# main.net
KiCad netlist of a schematic drawn in EAGLE
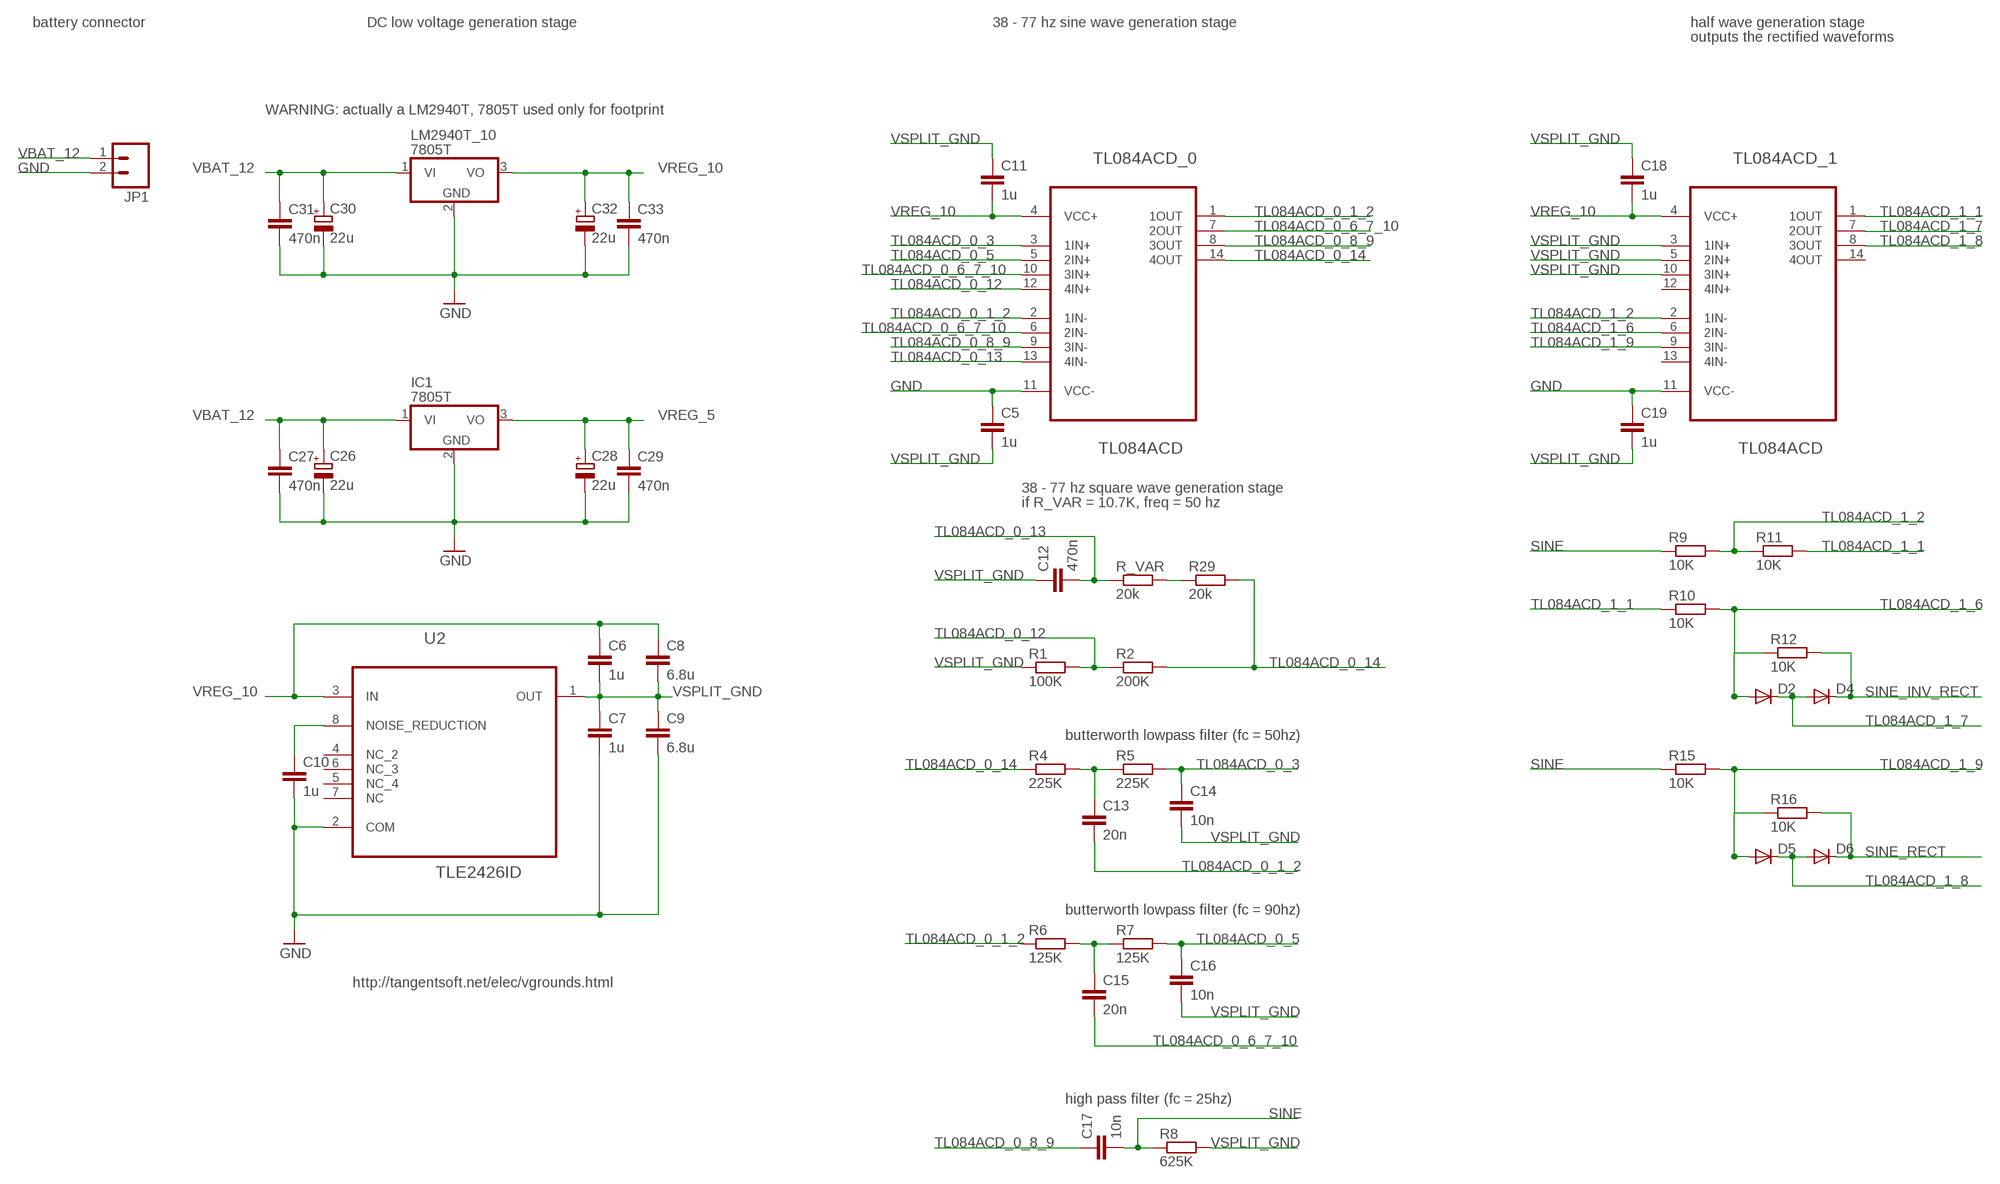
[diagram p0: schematic, sheet 1, part 1 of 2]
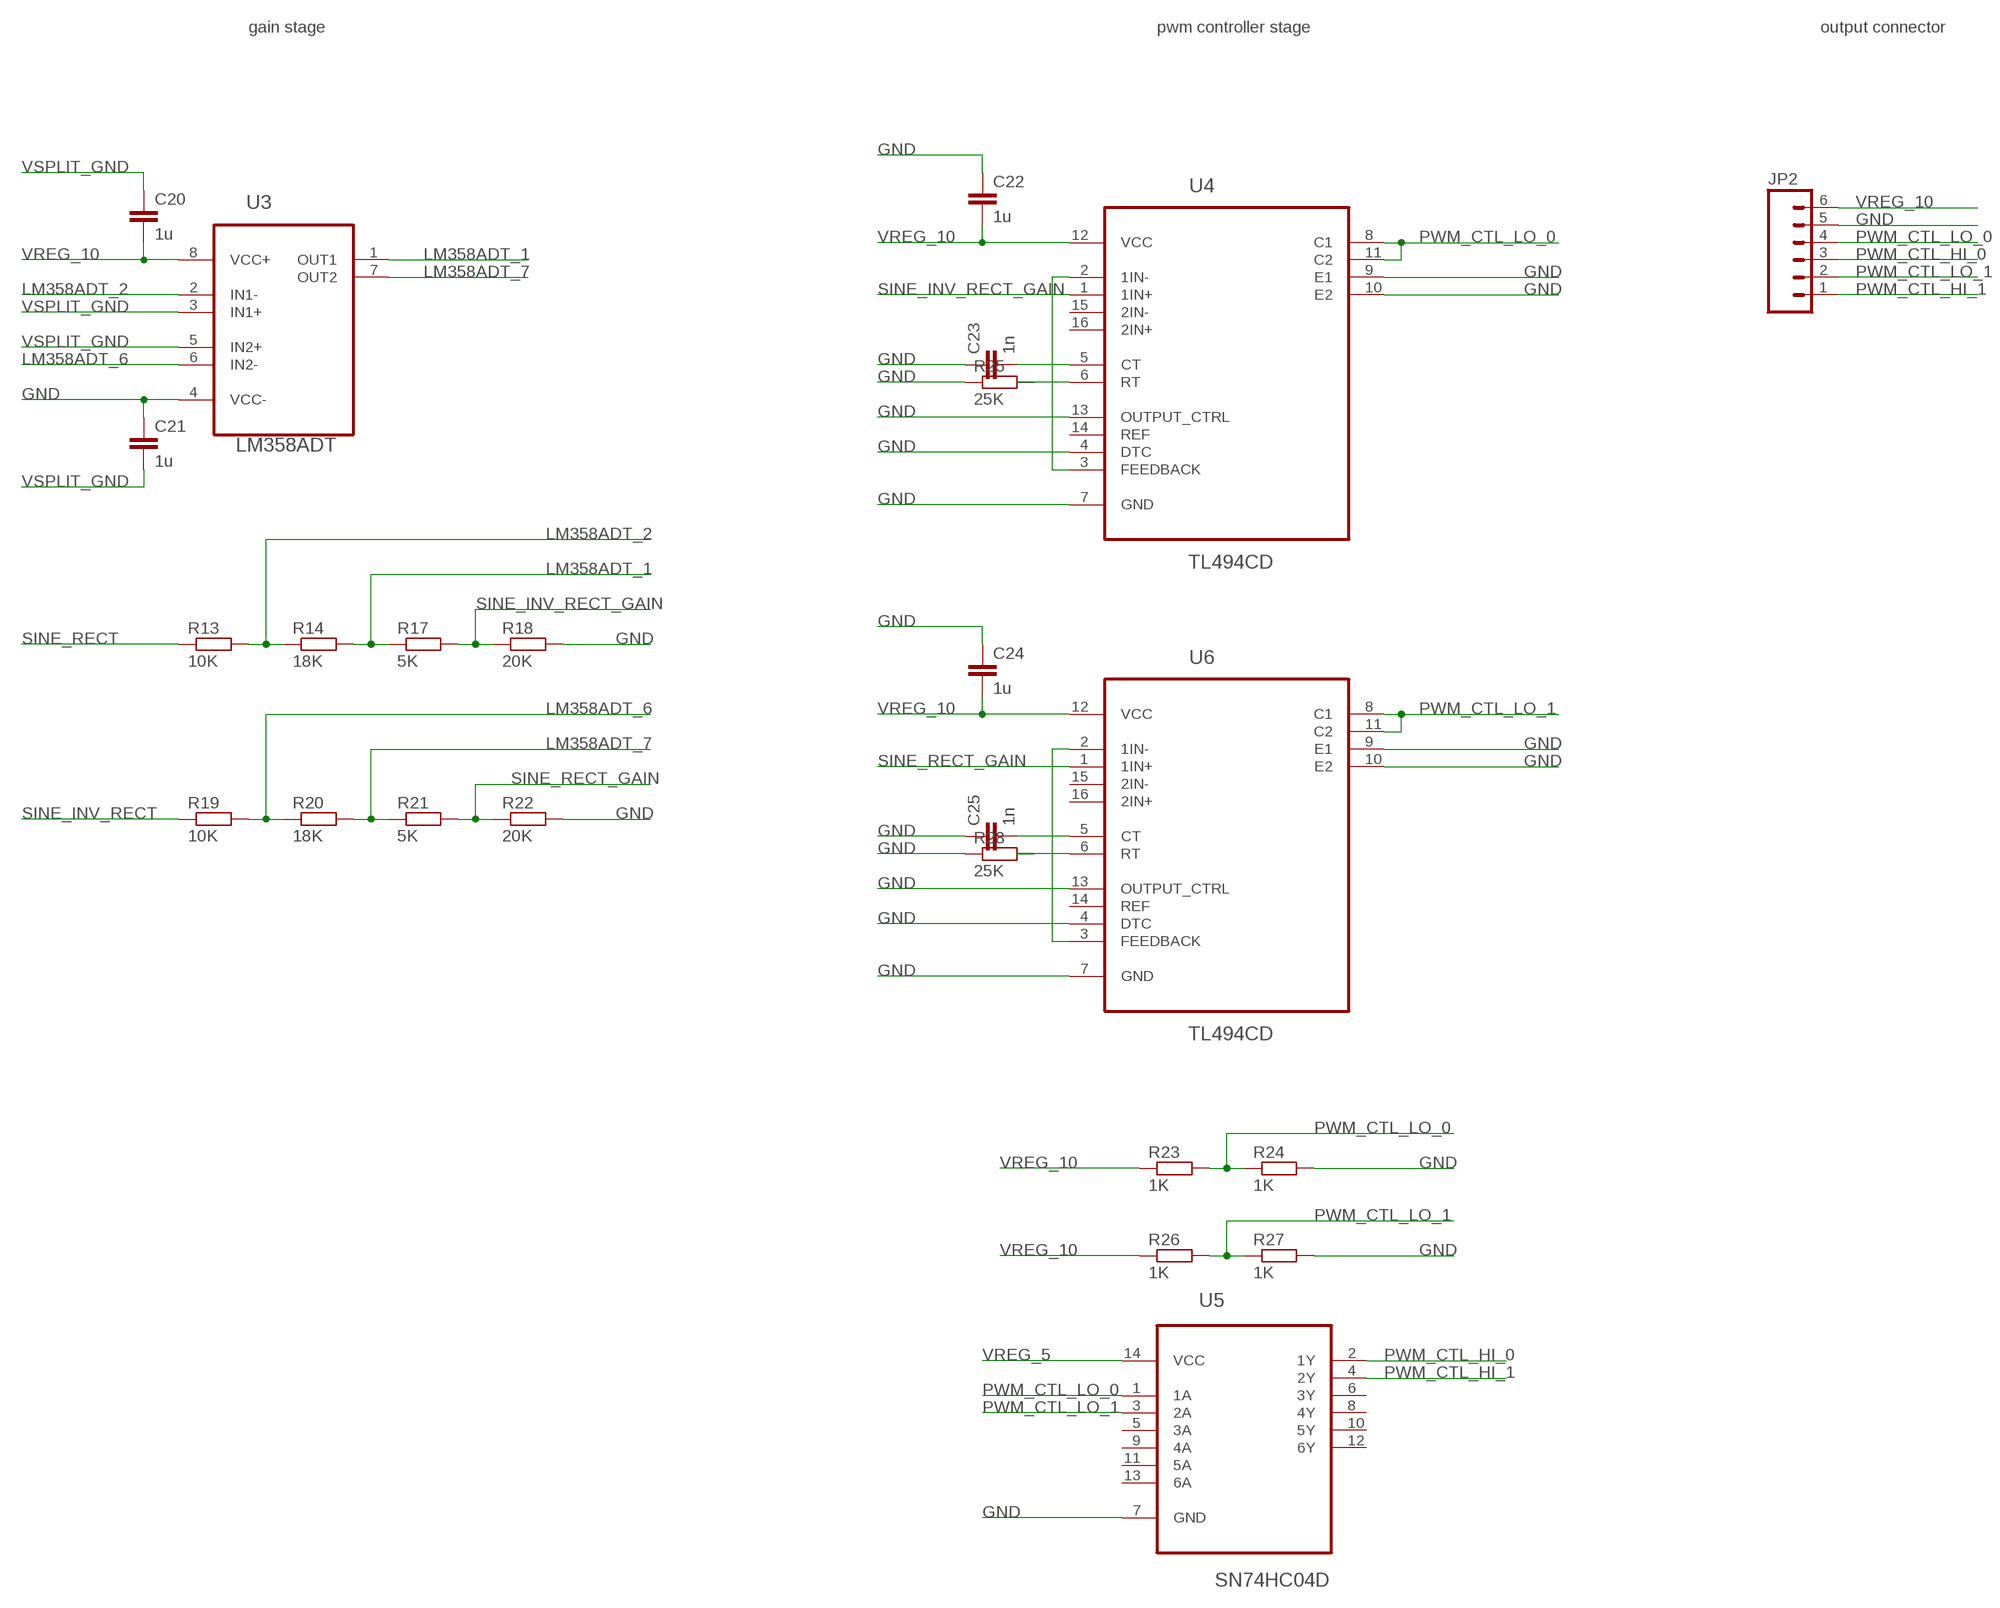
[diagram p1: schematic, sheet 1, part 2 of 2]

(export (version "E")
  (design (tool "Eeschema 10.0.6"))
  (components
    (comp (ref "C5")
      (value "1u")
      (footprint "eagle-import:C1206")
      (libsource (lib "eagle-import") (part "C-EUC1206"))
    )
    (comp (ref "C6")
      (value "1u")
      (footprint "eagle-import:C1206")
      (libsource (lib "eagle-import") (part "C-EUC1206"))
    )
    (comp (ref "C7")
      (value "1u")
      (footprint "eagle-import:C1206")
      (libsource (lib "eagle-import") (part "C-EUC1206"))
    )
    (comp (ref "C8")
      (value "6.8u")
      (footprint "eagle-import:C1206")
      (libsource (lib "eagle-import") (part "C-EUC1206"))
    )
    (comp (ref "C9")
      (value "6.8u")
      (footprint "eagle-import:C1206")
      (libsource (lib "eagle-import") (part "C-EUC1206"))
    )
    (comp (ref "C10")
      (value "1u")
      (footprint "eagle-import:C1206")
      (libsource (lib "eagle-import") (part "C-EUC1206"))
    )
    (comp (ref "C11")
      (value "1u")
      (footprint "eagle-import:C1206")
      (libsource (lib "eagle-import") (part "C-EUC1206"))
    )
    (comp (ref "C12")
      (value "470n")
      (footprint "eagle-import:C1206")
      (libsource (lib "eagle-import") (part "C-EUC1206"))
    )
    (comp (ref "C13")
      (value "20n")
      (footprint "eagle-import:C1206")
      (libsource (lib "eagle-import") (part "C-EUC1206"))
    )
    (comp (ref "C14")
      (value "10n")
      (footprint "eagle-import:C1206")
      (libsource (lib "eagle-import") (part "C-EUC1206"))
    )
    (comp (ref "C15")
      (value "20n")
      (footprint "eagle-import:C1206")
      (libsource (lib "eagle-import") (part "C-EUC1206"))
    )
    (comp (ref "C16")
      (value "10n")
      (footprint "eagle-import:C1206")
      (libsource (lib "eagle-import") (part "C-EUC1206"))
    )
    (comp (ref "C17")
      (value "10n")
      (footprint "eagle-import:C1206")
      (libsource (lib "eagle-import") (part "C-EUC1206"))
    )
    (comp (ref "C18")
      (value "1u")
      (footprint "eagle-import:C1206")
      (libsource (lib "eagle-import") (part "C-EUC1206"))
    )
    (comp (ref "C19")
      (value "1u")
      (footprint "eagle-import:C1206")
      (libsource (lib "eagle-import") (part "C-EUC1206"))
    )
    (comp (ref "C20")
      (value "1u")
      (footprint "eagle-import:C1206")
      (libsource (lib "eagle-import") (part "C-EUC1206"))
    )
    (comp (ref "C21")
      (value "1u")
      (footprint "eagle-import:C1206")
      (libsource (lib "eagle-import") (part "C-EUC1206"))
    )
    (comp (ref "C22")
      (value "1u")
      (footprint "eagle-import:C1206")
      (libsource (lib "eagle-import") (part "C-EUC1206"))
    )
    (comp (ref "C23")
      (value "1n")
      (footprint "eagle-import:C1206")
      (libsource (lib "eagle-import") (part "C-EUC1206"))
    )
    (comp (ref "C24")
      (value "1u")
      (footprint "eagle-import:C1206")
      (libsource (lib "eagle-import") (part "C-EUC1206"))
    )
    (comp (ref "C25")
      (value "1n")
      (footprint "eagle-import:C1206")
      (libsource (lib "eagle-import") (part "C-EUC1206"))
    )
    (comp (ref "C26")
      (value "22u")
      (footprint "eagle-import:085CS_1AR")
      (libsource (lib "eagle-import") (part "CPOL-EU085CS-1AR"))
    )
    (comp (ref "C27")
      (value "470n")
      (footprint "eagle-import:C1206")
      (libsource (lib "eagle-import") (part "C-EUC1206"))
    )
    (comp (ref "C28")
      (value "22u")
      (footprint "eagle-import:085CS_1AR")
      (libsource (lib "eagle-import") (part "CPOL-EU085CS-1AR"))
    )
    (comp (ref "C29")
      (value "470n")
      (footprint "eagle-import:C1206")
      (libsource (lib "eagle-import") (part "C-EUC1206"))
    )
    (comp (ref "C30")
      (value "22u")
      (footprint "eagle-import:085CS_1AR")
      (libsource (lib "eagle-import") (part "CPOL-EU085CS-1AR"))
    )
    (comp (ref "C31")
      (value "470n")
      (footprint "eagle-import:C1206")
      (libsource (lib "eagle-import") (part "C-EUC1206"))
    )
    (comp (ref "C32")
      (value "22u")
      (footprint "eagle-import:085CS_1AR")
      (libsource (lib "eagle-import") (part "CPOL-EU085CS-1AR"))
    )
    (comp (ref "C33")
      (value "470n")
      (footprint "eagle-import:C1206")
      (libsource (lib "eagle-import") (part "C-EUC1206"))
    )
    (comp (ref "D2")
      (value "DIODE-SOD323-W")
      (footprint "eagle-import:SOD323-W")
      (libsource (lib "eagle-import") (part "DIODE-SOD323-W"))
    )
    (comp (ref "D4")
      (value "DIODE-SOD323-W")
      (footprint "eagle-import:SOD323-W")
      (libsource (lib "eagle-import") (part "DIODE-SOD323-W"))
    )
    (comp (ref "D5")
      (value "DIODE-SOD323-W")
      (footprint "eagle-import:SOD323-W")
      (libsource (lib "eagle-import") (part "DIODE-SOD323-W"))
    )
    (comp (ref "D6")
      (value "DIODE-SOD323-W")
      (footprint "eagle-import:SOD323-W")
      (libsource (lib "eagle-import") (part "DIODE-SOD323-W"))
    )
    (comp (ref "IC1")
      (value "7805T")
      (footprint "eagle-import:TO220H")
      (libsource (lib "eagle-import") (part "78T05"))
    )
    (comp (ref "JP1")
      (value "M02LOCK")
      (footprint "eagle-import:1X02_LOCK")
      (libsource (lib "eagle-import") (part "M02LOCK"))
    )
    (comp (ref "JP2")
      (value "M06LOCK")
      (footprint "eagle-import:1X06_LOCK")
      (libsource (lib "eagle-import") (part "M06LOCK"))
    )
    (comp (ref "LM2940T_10")
      (value "7805T")
      (footprint "eagle-import:TO220H")
      (libsource (lib "eagle-import") (part "78T05"))
    )
    (comp (ref "R1")
      (value "100K")
      (footprint "eagle-import:M1206")
      (libsource (lib "eagle-import") (part "R-EU_M1206"))
    )
    (comp (ref "R2")
      (value "200K")
      (footprint "eagle-import:M1206")
      (libsource (lib "eagle-import") (part "R-EU_M1206"))
    )
    (comp (ref "R4")
      (value "225K")
      (footprint "eagle-import:M1206")
      (libsource (lib "eagle-import") (part "R-EU_M1206"))
    )
    (comp (ref "R5")
      (value "225K")
      (footprint "eagle-import:M1206")
      (libsource (lib "eagle-import") (part "R-EU_M1206"))
    )
    (comp (ref "R6")
      (value "125K")
      (footprint "eagle-import:M1206")
      (libsource (lib "eagle-import") (part "R-EU_M1206"))
    )
    (comp (ref "R7")
      (value "125K")
      (footprint "eagle-import:M1206")
      (libsource (lib "eagle-import") (part "R-EU_M1206"))
    )
    (comp (ref "R8")
      (value "625K")
      (footprint "eagle-import:M1206")
      (libsource (lib "eagle-import") (part "R-EU_M1206"))
    )
    (comp (ref "R9")
      (value "10K")
      (footprint "eagle-import:M1206")
      (libsource (lib "eagle-import") (part "R-EU_M1206"))
    )
    (comp (ref "R10")
      (value "10K")
      (footprint "eagle-import:M1206")
      (libsource (lib "eagle-import") (part "R-EU_M1206"))
    )
    (comp (ref "R11")
      (value "10K")
      (footprint "eagle-import:M1206")
      (libsource (lib "eagle-import") (part "R-EU_M1206"))
    )
    (comp (ref "R12")
      (value "10K")
      (footprint "eagle-import:M1206")
      (libsource (lib "eagle-import") (part "R-EU_M1206"))
    )
    (comp (ref "R13")
      (value "10K")
      (footprint "eagle-import:M1206")
      (libsource (lib "eagle-import") (part "R-EU_M1206"))
    )
    (comp (ref "R14")
      (value "18K")
      (footprint "eagle-import:M1206")
      (libsource (lib "eagle-import") (part "R-EU_M1206"))
    )
    (comp (ref "R15")
      (value "10K")
      (footprint "eagle-import:M1206")
      (libsource (lib "eagle-import") (part "R-EU_M1206"))
    )
    (comp (ref "R16")
      (value "10K")
      (footprint "eagle-import:M1206")
      (libsource (lib "eagle-import") (part "R-EU_M1206"))
    )
    (comp (ref "R17")
      (value "5K")
      (footprint "eagle-import:M1206")
      (libsource (lib "eagle-import") (part "R-EU_M1206"))
    )
    (comp (ref "R18")
      (value "20K")
      (footprint "eagle-import:M1206")
      (libsource (lib "eagle-import") (part "R-EU_M1206"))
    )
    (comp (ref "R19")
      (value "10K")
      (footprint "eagle-import:M1206")
      (libsource (lib "eagle-import") (part "R-EU_M1206"))
    )
    (comp (ref "R20")
      (value "18K")
      (footprint "eagle-import:M1206")
      (libsource (lib "eagle-import") (part "R-EU_M1206"))
    )
    (comp (ref "R21")
      (value "5K")
      (footprint "eagle-import:M1206")
      (libsource (lib "eagle-import") (part "R-EU_M1206"))
    )
    (comp (ref "R22")
      (value "20K")
      (footprint "eagle-import:M1206")
      (libsource (lib "eagle-import") (part "R-EU_M1206"))
    )
    (comp (ref "R23")
      (value "1K")
      (footprint "eagle-import:M1206")
      (libsource (lib "eagle-import") (part "R-EU_M1206"))
    )
    (comp (ref "R24")
      (value "1K")
      (footprint "eagle-import:M1206")
      (libsource (lib "eagle-import") (part "R-EU_M1206"))
    )
    (comp (ref "R25")
      (value "25K")
      (footprint "eagle-import:M1206")
      (libsource (lib "eagle-import") (part "R-EU_M1206"))
    )
    (comp (ref "R26")
      (value "1K")
      (footprint "eagle-import:M1206")
      (libsource (lib "eagle-import") (part "R-EU_M1206"))
    )
    (comp (ref "R27")
      (value "1K")
      (footprint "eagle-import:M1206")
      (libsource (lib "eagle-import") (part "R-EU_M1206"))
    )
    (comp (ref "R28")
      (value "25K")
      (footprint "eagle-import:M1206")
      (libsource (lib "eagle-import") (part "R-EU_M1206"))
    )
    (comp (ref "R29")
      (value "20k")
      (footprint "eagle-import:M1206")
      (libsource (lib "eagle-import") (part "R-EU_M1206"))
    )
    (comp (ref "R_VAR")
      (value "20k")
      (footprint "eagle-import:M1206")
      (libsource (lib "eagle-import") (part "R-EU_M1206"))
    )
    (comp (ref "TL084ACD_0")
      (value "TL084ACD")
      (footprint "eagle-import:SOIC127P600X175-14N")
      (libsource (lib "eagle-import") (part "TL084ACD"))
    )
    (comp (ref "TL084ACD_1")
      (value "TL084ACD")
      (footprint "eagle-import:SOIC127P600X175-14N")
      (libsource (lib "eagle-import") (part "TL084ACD"))
    )
    (comp (ref "U2")
      (value "TLE2426ID")
      (footprint "eagle-import:SOIC127P600X175-8N")
      (libsource (lib "eagle-import") (part "TLE2426ID"))
    )
    (comp (ref "U3")
      (value "LM358ADT")
      (footprint "eagle-import:SOIC127P600X175-8N")
      (libsource (lib "eagle-import") (part "LM358ADT"))
    )
    (comp (ref "U4")
      (value "TL494CD")
      (footprint "eagle-import:SOIC127P600X175-16N")
      (libsource (lib "eagle-import") (part "TL494CD"))
    )
    (comp (ref "U5")
      (value "SN74HC04D")
      (footprint "eagle-import:SOIC127P600X175-14N")
      (libsource (lib "eagle-import") (part "SN74HC04D"))
    )
    (comp (ref "U6")
      (value "TL494CD")
      (footprint "eagle-import:SOIC127P600X175-16N")
      (libsource (lib "eagle-import") (part "TL494CD"))
    )
  )
  (nets
    (net (code "1") (name "/LM358ADT_1") (class "Default")
      (node (ref "R14") (pin "2") (pinfunction "2_2") (pintype "passive"))
      (node (ref "R17") (pin "1") (pinfunction "1_1") (pintype "passive"))
      (node (ref "U3") (pin "1") (pinfunction "OUT1_1") (pintype "output"))
    )
    (net (code "2") (name "/LM358ADT_2") (class "Default")
      (node (ref "R13") (pin "2") (pinfunction "2_2") (pintype "passive"))
      (node (ref "R14") (pin "1") (pinfunction "1_1") (pintype "passive"))
      (node (ref "U3") (pin "2") (pinfunction "IN1-_2") (pintype "input"))
    )
    (net (code "3") (name "/LM358ADT_6") (class "Default")
      (node (ref "R19") (pin "2") (pinfunction "2_2") (pintype "passive"))
      (node (ref "R20") (pin "1") (pinfunction "1_1") (pintype "passive"))
      (node (ref "U3") (pin "6") (pinfunction "IN2-_6") (pintype "input"))
    )
    (net (code "4") (name "/LM358ADT_7") (class "Default")
      (node (ref "R20") (pin "2") (pinfunction "2_2") (pintype "passive"))
      (node (ref "R21") (pin "1") (pinfunction "1_1") (pintype "passive"))
      (node (ref "U3") (pin "7") (pinfunction "OUT2_7") (pintype "output"))
    )
    (net (code "5") (name "/PWM_CTL_HI_0") (class "Default")
      (node (ref "JP2") (pin "3") (pinfunction "3_3") (pintype "passive"))
      (node (ref "U5") (pin "2") (pinfunction "1Y_2") (pintype "output"))
    )
    (net (code "6") (name "/PWM_CTL_HI_1") (class "Default")
      (node (ref "JP2") (pin "1") (pinfunction "1_1") (pintype "passive"))
      (node (ref "U5") (pin "4") (pinfunction "2Y_4") (pintype "output"))
    )
    (net (code "7") (name "/PWM_CTL_LO_0") (class "Default")
      (node (ref "JP2") (pin "4") (pinfunction "4_4") (pintype "passive"))
      (node (ref "R23") (pin "2") (pinfunction "2_2") (pintype "passive"))
      (node (ref "R24") (pin "1") (pinfunction "1_1") (pintype "passive"))
      (node (ref "U4") (pin "11") (pinfunction "C2_11") (pintype "output"))
      (node (ref "U4") (pin "8") (pinfunction "C1_8") (pintype "output"))
      (node (ref "U5") (pin "1") (pinfunction "1A_1") (pintype "input"))
    )
    (net (code "8") (name "/PWM_CTL_LO_1") (class "Default")
      (node (ref "JP2") (pin "2") (pinfunction "2_2") (pintype "passive"))
      (node (ref "R26") (pin "2") (pinfunction "2_2") (pintype "passive"))
      (node (ref "R27") (pin "1") (pinfunction "1_1") (pintype "passive"))
      (node (ref "U5") (pin "3") (pinfunction "2A_3") (pintype "input"))
      (node (ref "U6") (pin "11") (pinfunction "C2_11") (pintype "output"))
      (node (ref "U6") (pin "8") (pinfunction "C1_8") (pintype "output"))
    )
    (net (code "9") (name "/SINE") (class "Default")
      (node (ref "C17") (pin "2") (pinfunction "2_2") (pintype "passive"))
      (node (ref "R15") (pin "1") (pinfunction "1_1") (pintype "passive"))
      (node (ref "R8") (pin "1") (pinfunction "1_1") (pintype "passive"))
      (node (ref "R9") (pin "1") (pinfunction "1_1") (pintype "passive"))
    )
    (net (code "10") (name "/SINE_INV_RECT") (class "Default")
      (node (ref "D4") (pin "C") (pinfunction "C_C") (pintype "passive"))
      (node (ref "R12") (pin "2") (pinfunction "2_2") (pintype "passive"))
      (node (ref "R19") (pin "1") (pinfunction "1_1") (pintype "passive"))
    )
    (net (code "11") (name "/SINE_INV_RECT_GAIN") (class "Default")
      (node (ref "R17") (pin "2") (pinfunction "2_2") (pintype "passive"))
      (node (ref "R18") (pin "1") (pinfunction "1_1") (pintype "passive"))
      (node (ref "U4") (pin "1") (pinfunction "1IN+_1") (pintype "input"))
    )
    (net (code "12") (name "/SINE_RECT") (class "Default")
      (node (ref "D6") (pin "C") (pinfunction "C_C") (pintype "passive"))
      (node (ref "R13") (pin "1") (pinfunction "1_1") (pintype "passive"))
      (node (ref "R16") (pin "2") (pinfunction "2_2") (pintype "passive"))
    )
    (net (code "13") (name "/SINE_RECT_GAIN") (class "Default")
      (node (ref "R21") (pin "2") (pinfunction "2_2") (pintype "passive"))
      (node (ref "R22") (pin "1") (pinfunction "1_1") (pintype "passive"))
      (node (ref "U6") (pin "1") (pinfunction "1IN+_1") (pintype "input"))
    )
    (net (code "14") (name "/TL084ACD_0_1_2") (class "Default")
      (node (ref "C13") (pin "2") (pinfunction "2_2") (pintype "passive"))
      (node (ref "R6") (pin "1") (pinfunction "1_1") (pintype "passive"))
      (node (ref "TL084ACD_0") (pin "1") (pinfunction "1OUT_1") (pintype "output"))
      (node (ref "TL084ACD_0") (pin "2") (pinfunction "1IN-_2") (pintype "input"))
    )
    (net (code "15") (name "/TL084ACD_0_3") (class "Default")
      (node (ref "C14") (pin "1") (pinfunction "1_1") (pintype "passive"))
      (node (ref "R5") (pin "2") (pinfunction "2_2") (pintype "passive"))
      (node (ref "TL084ACD_0") (pin "3") (pinfunction "1IN+_3") (pintype "input"))
    )
    (net (code "16") (name "/TL084ACD_0_5") (class "Default")
      (node (ref "C16") (pin "1") (pinfunction "1_1") (pintype "passive"))
      (node (ref "R7") (pin "2") (pinfunction "2_2") (pintype "passive"))
      (node (ref "TL084ACD_0") (pin "5") (pinfunction "2IN+_5") (pintype "input"))
    )
    (net (code "17") (name "/TL084ACD_0_6_7_10") (class "Default")
      (node (ref "C15") (pin "2") (pinfunction "2_2") (pintype "passive"))
      (node (ref "TL084ACD_0") (pin "10") (pinfunction "3IN+_10") (pintype "input"))
      (node (ref "TL084ACD_0") (pin "6") (pinfunction "2IN-_6") (pintype "input"))
      (node (ref "TL084ACD_0") (pin "7") (pinfunction "2OUT_7") (pintype "output"))
    )
    (net (code "18") (name "/TL084ACD_0_8_9") (class "Default")
      (node (ref "C17") (pin "1") (pinfunction "1_1") (pintype "passive"))
      (node (ref "TL084ACD_0") (pin "8") (pinfunction "3OUT_8") (pintype "output"))
      (node (ref "TL084ACD_0") (pin "9") (pinfunction "3IN-_9") (pintype "input"))
    )
    (net (code "19") (name "/TL084ACD_0_12") (class "Default")
      (node (ref "R1") (pin "2") (pinfunction "2_2") (pintype "passive"))
      (node (ref "R2") (pin "1") (pinfunction "1_1") (pintype "passive"))
      (node (ref "TL084ACD_0") (pin "12") (pinfunction "4IN+_12") (pintype "input"))
    )
    (net (code "20") (name "/TL084ACD_0_13") (class "Default")
      (node (ref "C12") (pin "2") (pinfunction "2_2") (pintype "passive"))
      (node (ref "R_VAR") (pin "1") (pinfunction "1_1") (pintype "passive"))
      (node (ref "TL084ACD_0") (pin "13") (pinfunction "4IN-_13") (pintype "input"))
    )
    (net (code "21") (name "/TL084ACD_0_14") (class "Default")
      (node (ref "R2") (pin "2") (pinfunction "2_2") (pintype "passive"))
      (node (ref "R29") (pin "2") (pinfunction "2_2") (pintype "passive"))
      (node (ref "R4") (pin "1") (pinfunction "1_1") (pintype "passive"))
      (node (ref "TL084ACD_0") (pin "14") (pinfunction "4OUT_14") (pintype "output"))
    )
    (net (code "22") (name "/TL084ACD_1_1") (class "Default")
      (node (ref "R10") (pin "1") (pinfunction "1_1") (pintype "passive"))
      (node (ref "R11") (pin "2") (pinfunction "2_2") (pintype "passive"))
      (node (ref "TL084ACD_1") (pin "1") (pinfunction "1OUT_1") (pintype "output"))
    )
    (net (code "23") (name "/TL084ACD_1_2") (class "Default")
      (node (ref "R11") (pin "1") (pinfunction "1_1") (pintype "passive"))
      (node (ref "R9") (pin "2") (pinfunction "2_2") (pintype "passive"))
      (node (ref "TL084ACD_1") (pin "2") (pinfunction "1IN-_2") (pintype "input"))
    )
    (net (code "24") (name "/TL084ACD_1_6") (class "Default")
      (node (ref "D2") (pin "A") (pinfunction "A_A") (pintype "passive"))
      (node (ref "R10") (pin "2") (pinfunction "2_2") (pintype "passive"))
      (node (ref "R12") (pin "1") (pinfunction "1_1") (pintype "passive"))
      (node (ref "TL084ACD_1") (pin "6") (pinfunction "2IN-_6") (pintype "input"))
    )
    (net (code "25") (name "/TL084ACD_1_7") (class "Default")
      (node (ref "D2") (pin "C") (pinfunction "C_C") (pintype "passive"))
      (node (ref "D4") (pin "A") (pinfunction "A_A") (pintype "passive"))
      (node (ref "TL084ACD_1") (pin "7") (pinfunction "2OUT_7") (pintype "output"))
    )
    (net (code "26") (name "/TL084ACD_1_8") (class "Default")
      (node (ref "D5") (pin "C") (pinfunction "C_C") (pintype "passive"))
      (node (ref "D6") (pin "A") (pinfunction "A_A") (pintype "passive"))
      (node (ref "TL084ACD_1") (pin "8") (pinfunction "3OUT_8") (pintype "output"))
    )
    (net (code "27") (name "/TL084ACD_1_9") (class "Default")
      (node (ref "D5") (pin "A") (pinfunction "A_A") (pintype "passive"))
      (node (ref "R15") (pin "2") (pinfunction "2_2") (pintype "passive"))
      (node (ref "R16") (pin "1") (pinfunction "1_1") (pintype "passive"))
      (node (ref "TL084ACD_1") (pin "9") (pinfunction "3IN-_9") (pintype "input"))
    )
    (net (code "28") (name "/VBAT_12") (class "Default")
      (node (ref "C26") (pin "+") (pinfunction "+_+") (pintype "passive"))
      (node (ref "C27") (pin "1") (pinfunction "1_1") (pintype "passive"))
      (node (ref "C30") (pin "+") (pinfunction "+_+") (pintype "passive"))
      (node (ref "C31") (pin "1") (pinfunction "1_1") (pintype "passive"))
      (node (ref "IC1") (pin "1") (pinfunction "VI_1") (pintype "input"))
      (node (ref "JP1") (pin "1") (pinfunction "1_1") (pintype "passive"))
      (node (ref "LM2940T_10") (pin "1") (pinfunction "VI_1") (pintype "input"))
    )
    (net (code "29") (name "/VREG_5") (class "Default")
      (node (ref "C28") (pin "+") (pinfunction "+_+") (pintype "passive"))
      (node (ref "C29") (pin "1") (pinfunction "1_1") (pintype "passive"))
      (node (ref "IC1") (pin "3") (pinfunction "VO_3") (pintype "passive"))
      (node (ref "U5") (pin "14") (pinfunction "VCC_14") (pintype "power_in"))
    )
    (net (code "30") (name "/VREG_10") (class "Default")
      (node (ref "C11") (pin "2") (pinfunction "2_2") (pintype "passive"))
      (node (ref "C18") (pin "2") (pinfunction "2_2") (pintype "passive"))
      (node (ref "C20") (pin "2") (pinfunction "2_2") (pintype "passive"))
      (node (ref "C22") (pin "2") (pinfunction "2_2") (pintype "passive"))
      (node (ref "C24") (pin "2") (pinfunction "2_2") (pintype "passive"))
      (node (ref "C32") (pin "+") (pinfunction "+_+") (pintype "passive"))
      (node (ref "C33") (pin "1") (pinfunction "1_1") (pintype "passive"))
      (node (ref "C6") (pin "1") (pinfunction "1_1") (pintype "passive"))
      (node (ref "C8") (pin "1") (pinfunction "1_1") (pintype "passive"))
      (node (ref "JP2") (pin "6") (pinfunction "6_6") (pintype "passive"))
      (node (ref "LM2940T_10") (pin "3") (pinfunction "VO_3") (pintype "passive"))
      (node (ref "R23") (pin "1") (pinfunction "1_1") (pintype "passive"))
      (node (ref "R26") (pin "1") (pinfunction "1_1") (pintype "passive"))
      (node (ref "TL084ACD_0") (pin "4") (pinfunction "VCC+_4") (pintype "power_in"))
      (node (ref "TL084ACD_1") (pin "4") (pinfunction "VCC+_4") (pintype "power_in"))
      (node (ref "U2") (pin "3") (pinfunction "IN_3") (pintype "input"))
      (node (ref "U3") (pin "8") (pinfunction "VCC+_8") (pintype "power_in"))
      (node (ref "U4") (pin "12") (pinfunction "VCC_12") (pintype "power_in"))
      (node (ref "U6") (pin "12") (pinfunction "VCC_12") (pintype "power_in"))
    )
    (net (code "31") (name "/VSPLIT_GND") (class "Default")
      (node (ref "C11") (pin "1") (pinfunction "1_1") (pintype "passive"))
      (node (ref "C12") (pin "1") (pinfunction "1_1") (pintype "passive"))
      (node (ref "C14") (pin "2") (pinfunction "2_2") (pintype "passive"))
      (node (ref "C16") (pin "2") (pinfunction "2_2") (pintype "passive"))
      (node (ref "C18") (pin "1") (pinfunction "1_1") (pintype "passive"))
      (node (ref "C19") (pin "2") (pinfunction "2_2") (pintype "passive"))
      (node (ref "C20") (pin "1") (pinfunction "1_1") (pintype "passive"))
      (node (ref "C21") (pin "2") (pinfunction "2_2") (pintype "passive"))
      (node (ref "C5") (pin "2") (pinfunction "2_2") (pintype "passive"))
      (node (ref "C6") (pin "2") (pinfunction "2_2") (pintype "passive"))
      (node (ref "C7") (pin "1") (pinfunction "1_1") (pintype "passive"))
      (node (ref "C8") (pin "2") (pinfunction "2_2") (pintype "passive"))
      (node (ref "C9") (pin "1") (pinfunction "1_1") (pintype "passive"))
      (node (ref "R1") (pin "1") (pinfunction "1_1") (pintype "passive"))
      (node (ref "R8") (pin "2") (pinfunction "2_2") (pintype "passive"))
      (node (ref "TL084ACD_1") (pin "10") (pinfunction "3IN+_10") (pintype "input"))
      (node (ref "TL084ACD_1") (pin "3") (pinfunction "1IN+_3") (pintype "input"))
      (node (ref "TL084ACD_1") (pin "5") (pinfunction "2IN+_5") (pintype "input"))
      (node (ref "U2") (pin "1") (pinfunction "OUT_1") (pintype "output"))
      (node (ref "U3") (pin "3") (pinfunction "IN1+_3") (pintype "input"))
      (node (ref "U3") (pin "5") (pinfunction "IN2+_5") (pintype "input"))
    )
    (net (code "32") (name "GND") (class "Default")
      (node (ref "C10") (pin "2") (pinfunction "2_2") (pintype "passive"))
      (node (ref "C19") (pin "1") (pinfunction "1_1") (pintype "passive"))
      (node (ref "C21") (pin "1") (pinfunction "1_1") (pintype "passive"))
      (node (ref "C22") (pin "1") (pinfunction "1_1") (pintype "passive"))
      (node (ref "C23") (pin "1") (pinfunction "1_1") (pintype "passive"))
      (node (ref "C24") (pin "1") (pinfunction "1_1") (pintype "passive"))
      (node (ref "C25") (pin "1") (pinfunction "1_1") (pintype "passive"))
      (node (ref "C26") (pin "-") (pinfunction "-_-") (pintype "passive"))
      (node (ref "C27") (pin "2") (pinfunction "2_2") (pintype "passive"))
      (node (ref "C28") (pin "-") (pinfunction "-_-") (pintype "passive"))
      (node (ref "C29") (pin "2") (pinfunction "2_2") (pintype "passive"))
      (node (ref "C30") (pin "-") (pinfunction "-_-") (pintype "passive"))
      (node (ref "C31") (pin "2") (pinfunction "2_2") (pintype "passive"))
      (node (ref "C32") (pin "-") (pinfunction "-_-") (pintype "passive"))
      (node (ref "C33") (pin "2") (pinfunction "2_2") (pintype "passive"))
      (node (ref "C5") (pin "1") (pinfunction "1_1") (pintype "passive"))
      (node (ref "C7") (pin "2") (pinfunction "2_2") (pintype "passive"))
      (node (ref "C9") (pin "2") (pinfunction "2_2") (pintype "passive"))
      (node (ref "IC1") (pin "2") (pinfunction "GND_2") (pintype "passive"))
      (node (ref "JP1") (pin "2") (pinfunction "2_2") (pintype "passive"))
      (node (ref "JP2") (pin "5") (pinfunction "5_5") (pintype "passive"))
      (node (ref "LM2940T_10") (pin "2") (pinfunction "GND_2") (pintype "passive"))
      (node (ref "R18") (pin "2") (pinfunction "2_2") (pintype "passive"))
      (node (ref "R22") (pin "2") (pinfunction "2_2") (pintype "passive"))
      (node (ref "R24") (pin "2") (pinfunction "2_2") (pintype "passive"))
      (node (ref "R25") (pin "1") (pinfunction "1_1") (pintype "passive"))
      (node (ref "R27") (pin "2") (pinfunction "2_2") (pintype "passive"))
      (node (ref "R28") (pin "1") (pinfunction "1_1") (pintype "passive"))
      (node (ref "TL084ACD_0") (pin "11") (pinfunction "VCC-_11") (pintype "power_in"))
      (node (ref "TL084ACD_1") (pin "11") (pinfunction "VCC-_11") (pintype "power_in"))
      (node (ref "U2") (pin "2") (pinfunction "COM_2") (pintype "passive"))
      (node (ref "U3") (pin "4") (pinfunction "VCC-_4") (pintype "power_in"))
      (node (ref "U4") (pin "10") (pinfunction "E2_10") (pintype "output"))
      (node (ref "U4") (pin "13") (pinfunction "OUTPUT_CTRL_13") (pintype "passive"))
      (node (ref "U4") (pin "4") (pinfunction "DTC_4") (pintype "input"))
      (node (ref "U4") (pin "7") (pinfunction "GND_7") (pintype "passive"))
      (node (ref "U4") (pin "9") (pinfunction "E1_9") (pintype "output"))
      (node (ref "U5") (pin "7") (pinfunction "GND_7") (pintype "passive"))
      (node (ref "U6") (pin "10") (pinfunction "E2_10") (pintype "output"))
      (node (ref "U6") (pin "13") (pinfunction "OUTPUT_CTRL_13") (pintype "passive"))
      (node (ref "U6") (pin "4") (pinfunction "DTC_4") (pintype "input"))
      (node (ref "U6") (pin "7") (pinfunction "GND_7") (pintype "passive"))
      (node (ref "U6") (pin "9") (pinfunction "E1_9") (pintype "output"))
    )
    (net (code "33") (name "Net-(C13-Pad1)") (class "Default")
      (node (ref "C13") (pin "1") (pinfunction "1_1") (pintype "passive"))
      (node (ref "R4") (pin "2") (pinfunction "2_2") (pintype "passive"))
      (node (ref "R5") (pin "1") (pinfunction "1_1") (pintype "passive"))
    )
    (net (code "34") (name "Net-(C15-Pad1)") (class "Default")
      (node (ref "C15") (pin "1") (pinfunction "1_1") (pintype "passive"))
      (node (ref "R6") (pin "2") (pinfunction "2_2") (pintype "passive"))
      (node (ref "R7") (pin "1") (pinfunction "1_1") (pintype "passive"))
    )
    (net (code "35") (name "Net-(R29-Pad1)") (class "Default")
      (node (ref "R29") (pin "1") (pinfunction "1_1") (pintype "passive"))
      (node (ref "R_VAR") (pin "2") (pinfunction "2_2") (pintype "passive"))
    )
    (net (code "36") (name "Net-(U2-NOISE_REDUCTION)") (class "Default")
      (node (ref "C10") (pin "1") (pinfunction "1_1") (pintype "passive"))
      (node (ref "U2") (pin "8") (pinfunction "NOISE_REDUCTION_8") (pintype "passive"))
    )
    (net (code "37") (name "Net-(U4-1IN-)") (class "Default")
      (node (ref "U4") (pin "2") (pinfunction "1IN-_2") (pintype "input"))
      (node (ref "U4") (pin "3") (pinfunction "FEEDBACK_3") (pintype "input"))
    )
    (net (code "38") (name "Net-(U4-CT)") (class "Default")
      (node (ref "C23") (pin "2") (pinfunction "2_2") (pintype "passive"))
      (node (ref "U4") (pin "5") (pinfunction "CT_5") (pintype "input"))
    )
    (net (code "39") (name "Net-(U4-RT)") (class "Default")
      (node (ref "R25") (pin "2") (pinfunction "2_2") (pintype "passive"))
      (node (ref "U4") (pin "6") (pinfunction "RT_6") (pintype "input"))
    )
    (net (code "40") (name "Net-(U6-1IN-)") (class "Default")
      (node (ref "U6") (pin "2") (pinfunction "1IN-_2") (pintype "input"))
      (node (ref "U6") (pin "3") (pinfunction "FEEDBACK_3") (pintype "input"))
    )
    (net (code "41") (name "Net-(U6-CT)") (class "Default")
      (node (ref "C25") (pin "2") (pinfunction "2_2") (pintype "passive"))
      (node (ref "U6") (pin "5") (pinfunction "CT_5") (pintype "input"))
    )
    (net (code "42") (name "Net-(U6-RT)") (class "Default")
      (node (ref "R28") (pin "2") (pinfunction "2_2") (pintype "passive"))
      (node (ref "U6") (pin "6") (pinfunction "RT_6") (pintype "input"))
    )
    (net (code "43") (name "unconnected-(TL084ACD_1-4IN+-Pad12)") (class "Default")
      (node (ref "TL084ACD_1") (pin "12") (pinfunction "4IN+_12") (pintype "input"))
    )
    (net (code "44") (name "unconnected-(TL084ACD_1-4IN--Pad13)") (class "Default")
      (node (ref "TL084ACD_1") (pin "13") (pinfunction "4IN-_13") (pintype "input"))
    )
    (net (code "45") (name "unconnected-(TL084ACD_1-4OUT-Pad14)") (class "Default")
      (node (ref "TL084ACD_1") (pin "14") (pinfunction "4OUT_14") (pintype "output"))
    )
    (net (code "46") (name "unconnected-(U2-NC-Pad7)") (class "Default")
      (node (ref "U2") (pin "7") (pinfunction "NC_7") (pintype "no_connect"))
    )
    (net (code "47") (name "unconnected-(U2-NC_2-Pad4)") (class "Default")
      (node (ref "U2") (pin "4") (pinfunction "NC_2_4") (pintype "no_connect"))
    )
    (net (code "48") (name "unconnected-(U2-NC_3-Pad6)") (class "Default")
      (node (ref "U2") (pin "6") (pinfunction "NC_3_6") (pintype "no_connect"))
    )
    (net (code "49") (name "unconnected-(U2-NC_4-Pad5)") (class "Default")
      (node (ref "U2") (pin "5") (pinfunction "NC_4_5") (pintype "no_connect"))
    )
    (net (code "50") (name "unconnected-(U4-2IN+-Pad16)") (class "Default")
      (node (ref "U4") (pin "16") (pinfunction "2IN+_16") (pintype "input"))
    )
    (net (code "51") (name "unconnected-(U4-2IN--Pad15)") (class "Default")
      (node (ref "U4") (pin "15") (pinfunction "2IN-_15") (pintype "input"))
    )
    (net (code "52") (name "unconnected-(U4-REF-Pad14)") (class "Default")
      (node (ref "U4") (pin "14") (pinfunction "REF_14") (pintype "input"))
    )
    (net (code "53") (name "unconnected-(U5-3A-Pad5)") (class "Default")
      (node (ref "U5") (pin "5") (pinfunction "3A_5") (pintype "input"))
    )
    (net (code "54") (name "unconnected-(U5-3Y-Pad6)") (class "Default")
      (node (ref "U5") (pin "6") (pinfunction "3Y_6") (pintype "output"))
    )
    (net (code "55") (name "unconnected-(U5-4A-Pad9)") (class "Default")
      (node (ref "U5") (pin "9") (pinfunction "4A_9") (pintype "input"))
    )
    (net (code "56") (name "unconnected-(U5-4Y-Pad8)") (class "Default")
      (node (ref "U5") (pin "8") (pinfunction "4Y_8") (pintype "output"))
    )
    (net (code "57") (name "unconnected-(U5-5A-Pad11)") (class "Default")
      (node (ref "U5") (pin "11") (pinfunction "5A_11") (pintype "input"))
    )
    (net (code "58") (name "unconnected-(U5-5Y-Pad10)") (class "Default")
      (node (ref "U5") (pin "10") (pinfunction "5Y_10") (pintype "output"))
    )
    (net (code "59") (name "unconnected-(U5-6A-Pad13)") (class "Default")
      (node (ref "U5") (pin "13") (pinfunction "6A_13") (pintype "input"))
    )
    (net (code "60") (name "unconnected-(U5-6Y-Pad12)") (class "Default")
      (node (ref "U5") (pin "12") (pinfunction "6Y_12") (pintype "output"))
    )
    (net (code "61") (name "unconnected-(U6-2IN+-Pad16)") (class "Default")
      (node (ref "U6") (pin "16") (pinfunction "2IN+_16") (pintype "input"))
    )
    (net (code "62") (name "unconnected-(U6-2IN--Pad15)") (class "Default")
      (node (ref "U6") (pin "15") (pinfunction "2IN-_15") (pintype "input"))
    )
    (net (code "63") (name "unconnected-(U6-REF-Pad14)") (class "Default")
      (node (ref "U6") (pin "14") (pinfunction "REF_14") (pintype "input"))
    )
  )
)
